# PWM.net
KiCad netlist of a schematic drawn in Altium Designer
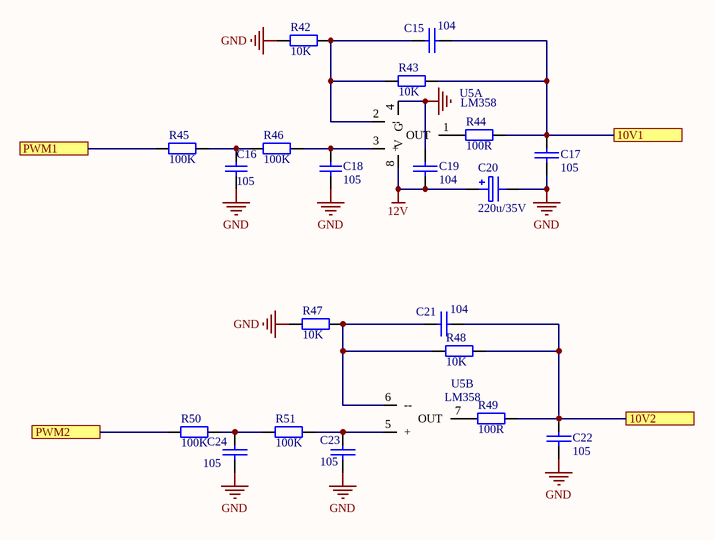
[diagram p0: PWM.SchDoc]

(export (version "E")
  (design (tool "Eeschema 10.0.6"))
  (components
    (comp (ref "C15")
      (value "104")
      (footprint "C0805C")
      (description "Capacitor")
      (libsource (lib "*") (part "CAP"))
    )
    (comp (ref "C16")
      (value "105")
      (footprint "c0805c")
      (description "Capacitor")
      (fields (field (name "PUBLISHER") "Altium Limited"))
      (libsource (lib "*") (part "Cap"))
    )
    (comp (ref "C17")
      (value "105")
      (footprint "C0805C")
      (description "Capacitor")
      (libsource (lib "*") (part "CAP"))
    )
    (comp (ref "C18")
      (value "105")
      (footprint "c0805c")
      (description "Capacitor")
      (fields (field (name "PUBLISHER") "Altium Limited"))
      (libsource (lib "*") (part "Cap"))
    )
    (comp (ref "C19")
      (value "104")
      (footprint "C0805C")
      (description "Capacitor")
      (libsource (lib "*") (part "CAP"))
    )
    (comp (ref "C20")
      (value "220u/35V")
      (footprint "E8MM")
      (description "Electrolytic Capacitor")
      (libsource (lib "*") (part "ELECTRO1"))
    )
    (comp (ref "C21")
      (value "104")
      (footprint "C0805C")
      (description "Capacitor")
      (libsource (lib "*") (part "CAP"))
    )
    (comp (ref "C22")
      (value "105")
      (footprint "C0805C")
      (description "Capacitor")
      (libsource (lib "*") (part "CAP"))
    )
    (comp (ref "C23")
      (value "105")
      (footprint "C0805C")
      (description "Capacitor")
      (libsource (lib "*") (part "CAP"))
    )
    (comp (ref "C24")
      (value "105")
      (footprint "C0805C")
      (description "Capacitor")
      (libsource (lib "*") (part "CAP"))
    )
    (comp (ref "R42")
      (value "10K")
      (footprint "0805R")
      (description "Resistor")
      (fields (field (name "PUBLISHER") "Altium Limited"))
      (libsource (lib "Miscellaneous Devices") (part "res"))
    )
    (comp (ref "R43")
      (value "10K")
      (footprint "0805R")
      (description "Resistor")
      (fields (field (name "PUBLISHER") "Altium Limited"))
      (libsource (lib "Miscellaneous Devices") (part "res"))
    )
    (comp (ref "R44")
      (value "100R")
      (footprint "0805R")
      (description "Resistor")
      (fields (field (name "PUBLISHER") "Altium Limited"))
      (libsource (lib "Miscellaneous Devices") (part "res"))
    )
    (comp (ref "R45")
      (value "100K")
      (footprint "0805R")
      (description "Resistor")
      (fields (field (name "PUBLISHER") "Altium Limited"))
      (libsource (lib "Miscellaneous Devices") (part "res"))
    )
    (comp (ref "R46")
      (value "100K")
      (footprint "0805R")
      (description "Resistor")
      (fields (field (name "PUBLISHER") "Altium Limited"))
      (libsource (lib "Miscellaneous Devices") (part "res"))
    )
    (comp (ref "R47")
      (value "10K")
      (footprint "0805R")
      (description "Resistor")
      (fields (field (name "PUBLISHER") "Altium Limited"))
      (libsource (lib "Miscellaneous Devices") (part "res"))
    )
    (comp (ref "R48")
      (value "10K")
      (footprint "0805R")
      (description "Resistor")
      (fields (field (name "PUBLISHER") "Altium Limited"))
      (libsource (lib "Miscellaneous Devices") (part "res"))
    )
    (comp (ref "R49")
      (value "100R")
      (footprint "0805R")
      (description "Resistor")
      (fields (field (name "PUBLISHER") "Altium Limited"))
      (libsource (lib "Miscellaneous Devices") (part "res"))
    )
    (comp (ref "R50")
      (value "100K")
      (footprint "0805R")
      (description "Resistor")
      (fields (field (name "PUBLISHER") "Altium Limited"))
      (libsource (lib "Miscellaneous Devices") (part "res"))
    )
    (comp (ref "R51")
      (value "100K")
      (footprint "0805R")
      (description "Resistor")
      (fields (field (name "PUBLISHER") "Altium Limited"))
      (libsource (lib "Miscellaneous Devices") (part "res"))
    )
    (comp (ref "U5") (value "LM358") (footprint "SOP-08") (libsource (lib "*") (part "LM358")))
  )
  (nets
    (net (code "1") (name "/10V1") (class "Default")
      (node (ref "C15") (pin "2") (pinfunction "2_2") (pintype "passive"))
      (node (ref "C17") (pin "1") (pinfunction "1_1") (pintype "passive"))
      (node (ref "R43") (pin "1") (pinfunction "1_1") (pintype "passive"))
      (node (ref "R44") (pin "1") (pinfunction "1_1") (pintype "passive"))
    )
    (net (code "2") (name "/10V2") (class "Default")
      (node (ref "C21") (pin "2") (pinfunction "2_2") (pintype "passive"))
      (node (ref "C22") (pin "1") (pinfunction "1_1") (pintype "passive"))
      (node (ref "R48") (pin "1") (pinfunction "1_1") (pintype "passive"))
      (node (ref "R49") (pin "1") (pinfunction "1_1") (pintype "passive"))
    )
    (net (code "3") (name "/PWM1") (class "Default")
      (node (ref "R45") (pin "2") (pinfunction "2_2") (pintype "passive"))
    )
    (net (code "4") (name "/PWM2") (class "Default")
      (node (ref "R50") (pin "2") (pinfunction "2_2") (pintype "passive"))
    )
    (net (code "5") (name "12V") (class "Default")
      (node (ref "C19") (pin "2") (pinfunction "2_2") (pintype "passive"))
      (node (ref "C20") (pin "1") (pinfunction "1_1") (pintype "passive"))
      (node (ref "U5") (pin "8") (pinfunction "V_8") (pintype "passive"))
    )
    (net (code "6") (name "GND") (class "Default")
      (node (ref "C16") (pin "1") (pinfunction "1_1") (pintype "passive"))
      (node (ref "C17") (pin "2") (pinfunction "2_2") (pintype "passive"))
      (node (ref "C18") (pin "1") (pinfunction "1_1") (pintype "passive"))
      (node (ref "C19") (pin "1") (pinfunction "1_1") (pintype "passive"))
      (node (ref "C20") (pin "2") (pinfunction "2_2") (pintype "passive"))
      (node (ref "C22") (pin "2") (pinfunction "2_2") (pintype "passive"))
      (node (ref "C23") (pin "2") (pinfunction "2_2") (pintype "passive"))
      (node (ref "C24") (pin "2") (pinfunction "2_2") (pintype "passive"))
      (node (ref "R42") (pin "2") (pinfunction "2_2") (pintype "passive"))
      (node (ref "R47") (pin "2") (pinfunction "2_2") (pintype "passive"))
      (node (ref "U5") (pin "4") (pinfunction "G_4") (pintype "passive"))
    )
    (net (code "7") (name "Net-(C16-Pad2)") (class "Default")
      (node (ref "C16") (pin "2") (pinfunction "2_2") (pintype "passive"))
      (node (ref "R45") (pin "1") (pinfunction "1_1") (pintype "passive"))
      (node (ref "R46") (pin "2") (pinfunction "2_2") (pintype "passive"))
    )
    (net (code "8") (name "Net-(C24-Pad1)") (class "Default")
      (node (ref "C24") (pin "1") (pinfunction "1_1") (pintype "passive"))
      (node (ref "R50") (pin "1") (pinfunction "1_1") (pintype "passive"))
      (node (ref "R51") (pin "2") (pinfunction "2_2") (pintype "passive"))
    )
    (net (code "9") (name "Net-(U5A-+)") (class "Default")
      (node (ref "C18") (pin "2") (pinfunction "2_2") (pintype "passive"))
      (node (ref "R46") (pin "1") (pinfunction "1_1") (pintype "passive"))
      (node (ref "U5") (pin "3") (pinfunction "+_3") (pintype "passive"))
    )
    (net (code "10") (name "Net-(U5A---)") (class "Default")
      (node (ref "C15") (pin "1") (pinfunction "1_1") (pintype "passive"))
      (node (ref "R42") (pin "1") (pinfunction "1_1") (pintype "passive"))
      (node (ref "R43") (pin "2") (pinfunction "2_2") (pintype "passive"))
      (node (ref "U5") (pin "2") (pinfunction "--_2") (pintype "passive"))
    )
    (net (code "11") (name "Net-(U5A-OUT)") (class "Default")
      (node (ref "R44") (pin "2") (pinfunction "2_2") (pintype "passive"))
      (node (ref "U5") (pin "1") (pinfunction "OUT_1") (pintype "passive"))
    )
    (net (code "12") (name "Net-(U5B-+)") (class "Default")
      (node (ref "C23") (pin "1") (pinfunction "1_1") (pintype "passive"))
      (node (ref "R51") (pin "1") (pinfunction "1_1") (pintype "passive"))
      (node (ref "U5") (pin "5") (pinfunction "+_5") (pintype "passive"))
    )
    (net (code "13") (name "Net-(U5B---)") (class "Default")
      (node (ref "C21") (pin "1") (pinfunction "1_1") (pintype "passive"))
      (node (ref "R47") (pin "1") (pinfunction "1_1") (pintype "passive"))
      (node (ref "R48") (pin "2") (pinfunction "2_2") (pintype "passive"))
      (node (ref "U5") (pin "6") (pinfunction "--_6") (pintype "passive"))
    )
    (net (code "14") (name "Net-(U5B-OUT)") (class "Default")
      (node (ref "R49") (pin "2") (pinfunction "2_2") (pintype "passive"))
      (node (ref "U5") (pin "7") (pinfunction "OUT_7") (pintype "passive"))
    )
  )
)
